# TOP.net
KiCad netlist of a schematic drawn in Altium Designer
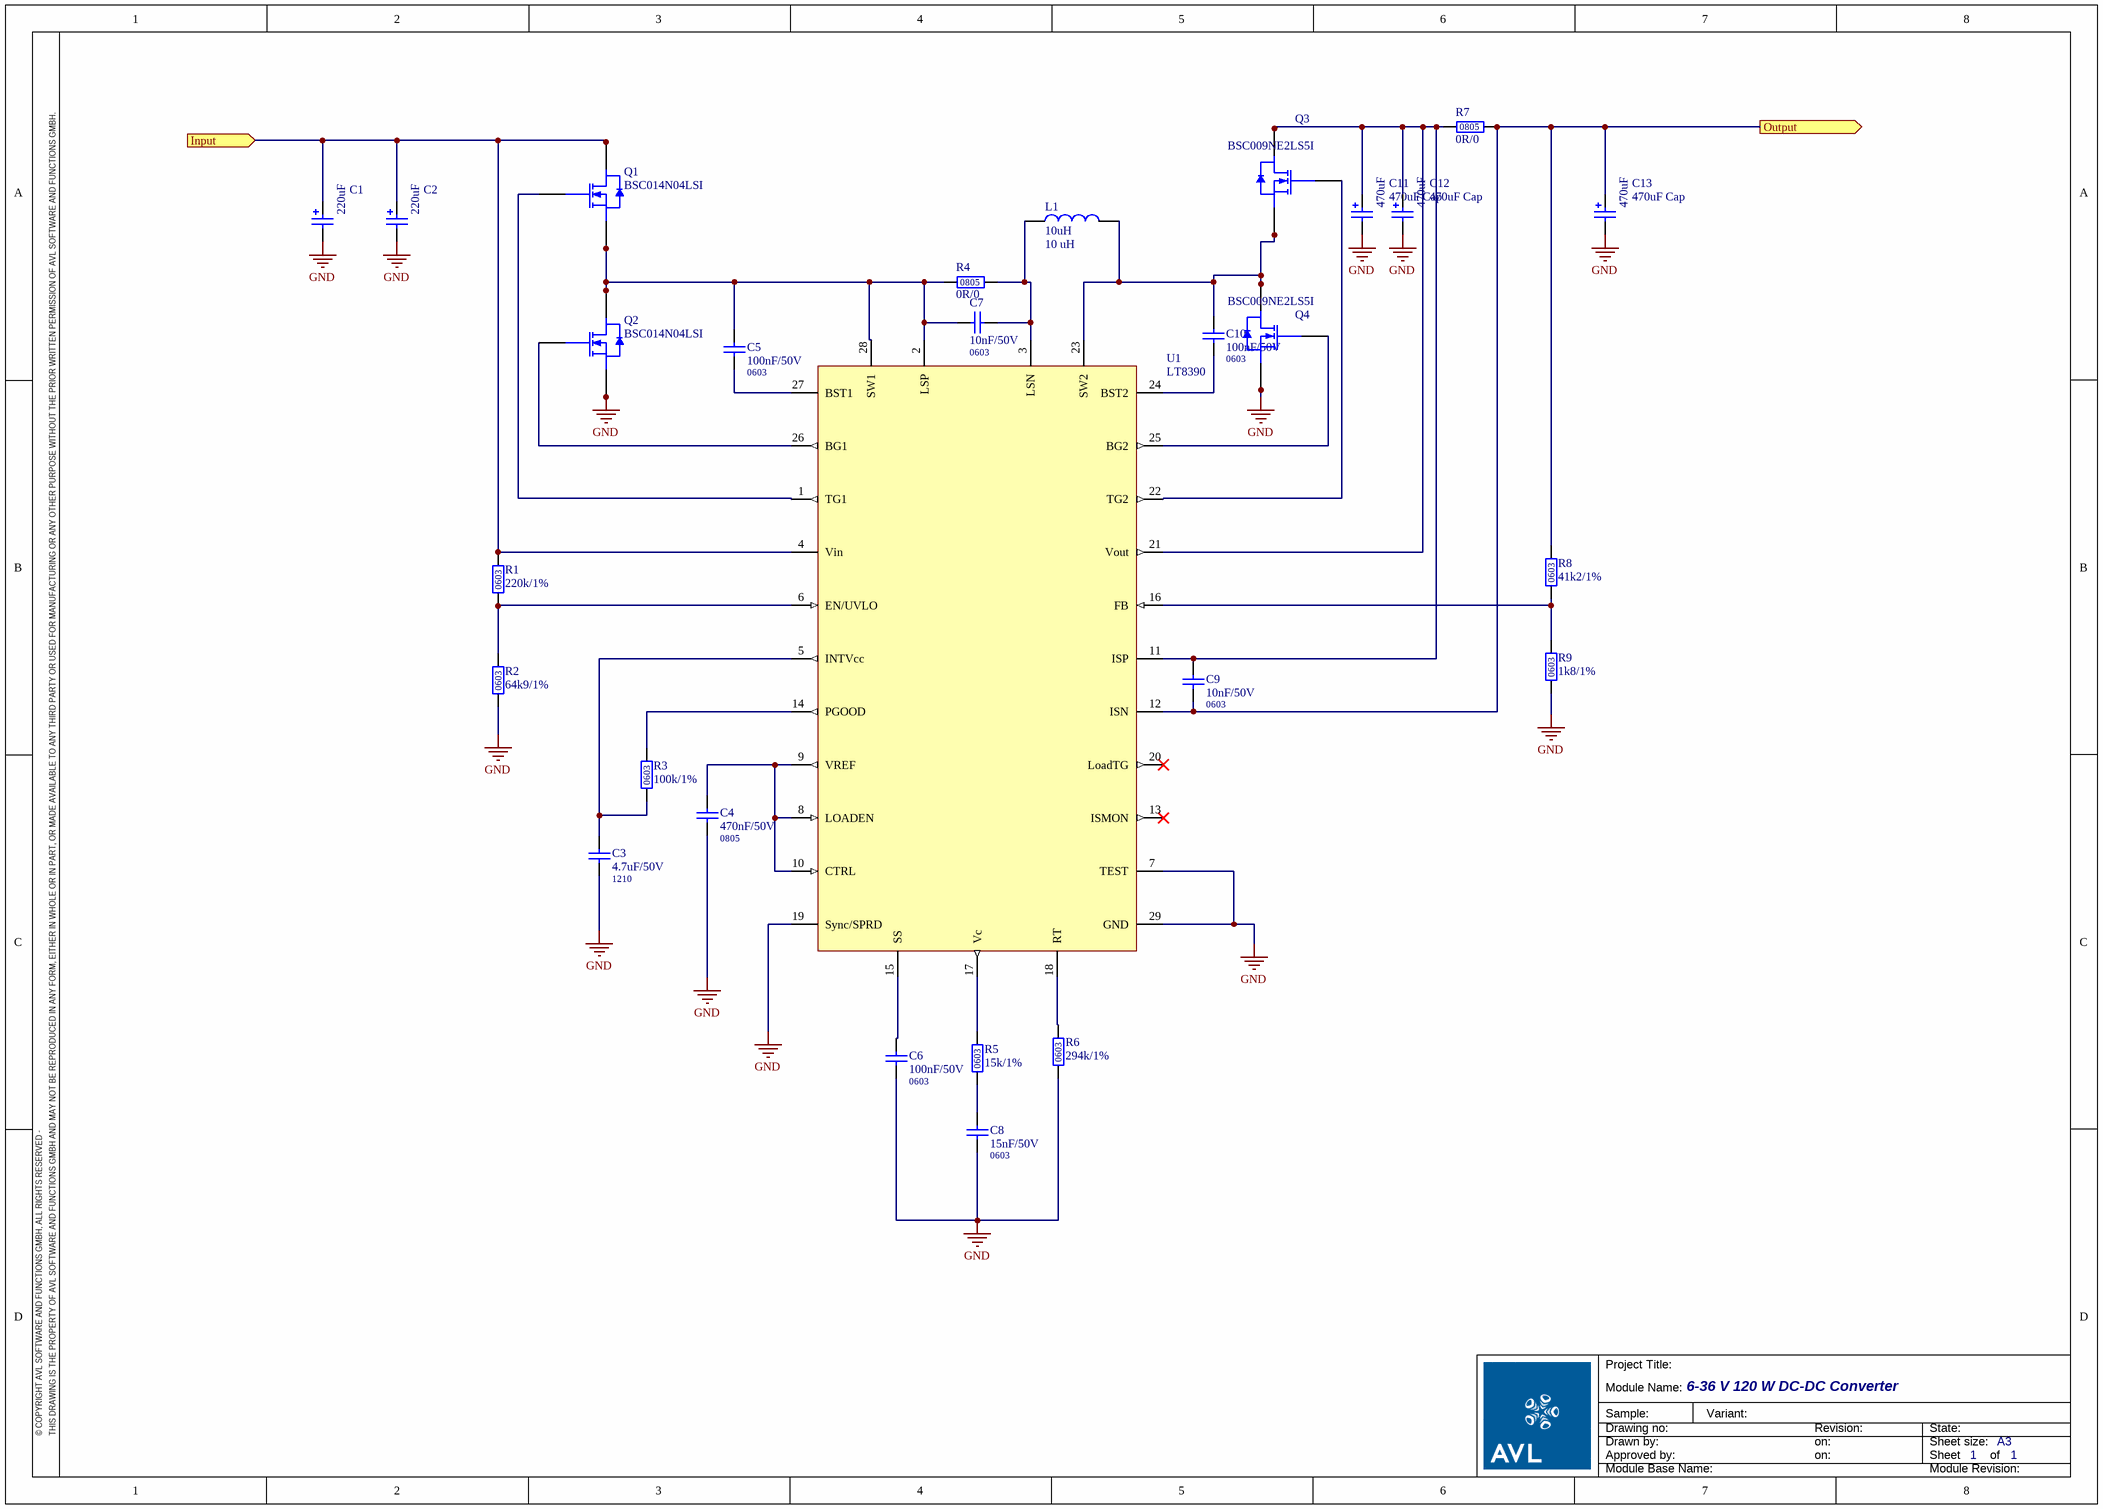
[diagram p0: TOP.SchDoc]

(export (version "E")
  (design (tool "Eeschema 10.0.6"))
  (components
    (comp (ref "C1")
      (value "220uF Cap")
      (footprint "PcbLib:WCAP-ASLI_4x5.5")
      (libsource (lib "SchLib") (part "220uF Cap"))
    )
    (comp (ref "C2")
      (value "220uF Cap")
      (footprint "PcbLib:WCAP-ASLI_4x5.5")
      (libsource (lib "SchLib") (part "220uF Cap"))
    )
    (comp (ref "C3")
      (value "4.7uF/50V")
      (footprint "CAPC3225X30")
      (fields
        (field (name "VOLTAGE") "50V")
        (field (name "PACKAGE") "1210")
        (field (name "PART_NUMBER") "0444.00103")
        (field (name "MANUFACTURER") "Murata")
      )
      (libsource (lib "AVL_EHW_Comp_Lib") (part "Capacitor"))
    )
    (comp (ref "C4")
      (value "470nF/50V")
      (footprint "CAPC2012X15")
      (fields
        (field (name "VOLTAGE") "50V")
        (field (name "PACKAGE") "0805")
        (field (name "PART_NUMBER") "0444.00090")
        (field (name "MANUFACTURER") "Murata")
      )
      (libsource (lib "AVL_EHW_Comp_Lib") (part "Capacitor"))
    )
    (comp (ref "C5")
      (value "100nF/50V")
      (footprint "CAPC1608X10")
      (fields
        (field (name "VOLTAGE") "50V")
        (field (name "PACKAGE") "0603")
        (field (name "PART_NUMBER") "0444.00073")
        (field (name "MANUFACTURER") "Murata")
      )
      (libsource (lib "AVL_EHW_Comp_Lib") (part "Capacitor"))
    )
    (comp (ref "C6")
      (value "100nF/50V")
      (footprint "CAPC1608X10")
      (fields
        (field (name "VOLTAGE") "50V")
        (field (name "PACKAGE") "0603")
        (field (name "PART_NUMBER") "0444.00073")
        (field (name "MANUFACTURER") "Murata")
      )
      (libsource (lib "AVL_EHW_Comp_Lib") (part "Capacitor"))
    )
    (comp (ref "C7")
      (value "10nF/50V")
      (footprint "CAPC1608X10")
      (fields
        (field (name "VOLTAGE") "50V")
        (field (name "PACKAGE") "0603")
        (field (name "PART_NUMBER") "0444.00053")
        (field (name "MANUFACTURER") "Murata")
      )
      (libsource (lib "AVL_EHW_Comp_Lib") (part "Capacitor"))
    )
    (comp (ref "C8")
      (value "15nF/50V")
      (footprint "CAPC1608X10")
      (fields
        (field (name "VOLTAGE") "50V")
        (field (name "PACKAGE") "0603")
        (field (name "PART_NUMBER") "0444.00059")
        (field (name "MANUFACTURER") "Murata")
      )
      (libsource (lib "AVL_EHW_Comp_Lib") (part "Capacitor"))
    )
    (comp (ref "C9")
      (value "10nF/50V")
      (footprint "CAPC1608X10")
      (fields
        (field (name "VOLTAGE") "50V")
        (field (name "PACKAGE") "0603")
        (field (name "PART_NUMBER") "0444.00053")
        (field (name "MANUFACTURER") "Murata")
      )
      (libsource (lib "AVL_EHW_Comp_Lib") (part "Capacitor"))
    )
    (comp (ref "C10")
      (value "100nF/50V")
      (footprint "CAPC1608X10")
      (fields
        (field (name "VOLTAGE") "50V")
        (field (name "PACKAGE") "0603")
        (field (name "PART_NUMBER") "0444.00073")
        (field (name "MANUFACTURER") "Murata")
      )
      (libsource (lib "AVL_EHW_Comp_Lib") (part "Capacitor"))
    )
    (comp (ref "C11")
      (value "470uF Cap")
      (footprint "PcbLib:WCAP-ASLL_4x5.5")
      (libsource (lib "SchLib") (part "470uF Cap"))
    )
    (comp (ref "C12")
      (value "470uF Cap")
      (footprint "PcbLib:WCAP-ASLL_4x5.5")
      (libsource (lib "SchLib") (part "470uF Cap"))
    )
    (comp (ref "C13")
      (value "470uF Cap")
      (footprint "PcbLib:WCAP-ASLL_4x5.5")
      (libsource (lib "SchLib") (part "470uF Cap"))
    )
    (comp (ref "L1")
      (value "10uH")
      (footprint "PcbLib:WE-HCF_2818")
      (description "WE-HCF SMD High Current Inductor, size 2818, 10 uH")
      (fields
        (field (name "PART NUMBER") "7443641000")
        (field (name "ALTIUM_VALUE") "10 uH")
        (field (name "PUBLISHER") "Wurth Elektronik")
      )
      (libsource (lib "SchLib") (part "10uH"))
    )
    (comp (ref "Q1")
      (value "BSC014N04LSI")
      (footprint "PcbLib:TDSON-8-FL")
      (libsource (lib "SchLib") (part "BSC014N04LSI"))
    )
    (comp (ref "Q2")
      (value "BSC014N04LSI")
      (footprint "PcbLib:TDSON-8-FL")
      (libsource (lib "SchLib") (part "BSC014N04LSI"))
    )
    (comp (ref "Q3")
      (value "BSC009NE2LS5I")
      (footprint "PcbLib:TDSON-8-FL")
      (libsource (lib "SchLib") (part "BSC009NE2LS5I"))
    )
    (comp (ref "Q4")
      (value "BSC009NE2LS5I")
      (footprint "PcbLib:TDSON-8-FL")
      (libsource (lib "SchLib") (part "BSC009NE2LS5I"))
    )
    (comp (ref "R1")
      (value "220k/1%")
      (footprint "RESC1608X05")
      (fields
        (field (name "TOLERANCE") "1%")
        (field (name "PACKAGE") "0603")
        (field (name "PART_NUMBER") "0440.00197")
        (field (name "MANUFACTURER") "Vishay")
      )
      (libsource (lib "AVL_EHW_Comp_Lib") (part "Resistor-Chip"))
    )
    (comp (ref "R2")
      (value "64k9/1%")
      (footprint "RESC1608X05")
      (fields
        (field (name "TOLERANCE") "1%")
        (field (name "PACKAGE") "0603")
        (field (name "PART_NUMBER") "0440.00282")
        (field (name "MANUFACTURER") "Vishay")
      )
      (libsource (lib "AVL_EHW_Comp_Lib") (part "Resistor-Chip"))
    )
    (comp (ref "R3")
      (value "100k/1%")
      (footprint "RESC1608X05")
      (fields
        (field (name "TOLERANCE") "1%")
        (field (name "PACKAGE") "0603")
        (field (name "PART_NUMBER") "0440.00176")
        (field (name "MANUFACTURER") "Vishay")
      )
      (libsource (lib "AVL_EHW_Comp_Lib") (part "Resistor-Chip"))
    )
    (comp (ref "R4")
      (value "0R/0")
      (footprint "RESC2012X05")
      (fields
        (field (name "TOLERANCE") "0")
        (field (name "PACKAGE") "0805")
        (field (name "PART_NUMBER") "0440.00003")
        (field (name "MANUFACTURER") "Vishay")
      )
      (libsource (lib "AVL_EHW_Comp_Lib") (part "Resistor-Chip"))
    )
    (comp (ref "R5")
      (value "15k/1%")
      (footprint "RESC1608X05")
      (fields
        (field (name "TOLERANCE") "1%")
        (field (name "PACKAGE") "0603")
        (field (name "PART_NUMBER") "0440.00148")
        (field (name "MANUFACTURER") "Vishay")
      )
      (libsource (lib "AVL_EHW_Comp_Lib") (part "Resistor-Chip"))
    )
    (comp (ref "R6")
      (value "294k/1%")
      (footprint "RESC1608X05")
      (fields
        (field (name "TOLERANCE") "1%")
        (field (name "PACKAGE") "0603")
        (field (name "PART_NUMBER") "0440.00329")
        (field (name "MANUFACTURER") "Vishay")
      )
      (libsource (lib "AVL_EHW_Comp_Lib") (part "Resistor-Chip"))
    )
    (comp (ref "R7")
      (value "0R/0")
      (footprint "RESC2012X05")
      (fields
        (field (name "TOLERANCE") "0")
        (field (name "PACKAGE") "0805")
        (field (name "PART_NUMBER") "0440.00003")
        (field (name "MANUFACTURER") "Vishay")
      )
      (libsource (lib "AVL_EHW_Comp_Lib") (part "Resistor-Chip"))
    )
    (comp (ref "R8")
      (value "41k2/1%")
      (footprint "RESC1608X05")
      (fields
        (field (name "TOLERANCE") "1%")
        (field (name "PACKAGE") "0603")
        (field (name "PART_NUMBER") "0440.00284")
        (field (name "MANUFACTURER") "Vishay")
      )
      (libsource (lib "AVL_EHW_Comp_Lib") (part "Resistor-Chip"))
    )
    (comp (ref "R9")
      (value "1k8/1%")
      (footprint "RESC1608X05")
      (fields
        (field (name "TOLERANCE") "1%")
        (field (name "PACKAGE") "0603")
        (field (name "PART_NUMBER") "0440.00105")
        (field (name "MANUFACTURER") "Vishay")
      )
      (libsource (lib "AVL_EHW_Comp_Lib") (part "Resistor-Chip"))
    )
    (comp (ref "U1")
      (value "LT8390")
      (footprint "LT3890")
      (libsource (lib "Schematic Components") (part "LT8390"))
    )
  )
  (nets
    (net (code "1") (name "/Input") (class "Default")
      (node (ref "C1") (pin "1") (pinfunction "P_1") (pintype "passive"))
      (node (ref "C2") (pin "1") (pinfunction "P_1") (pintype "passive"))
      (node (ref "Q1") (pin "5") (pinfunction "D_5") (pintype "passive"))
      (node (ref "Q1") (pin "6") (pinfunction "D_6") (pintype "passive"))
      (node (ref "Q1") (pin "7") (pinfunction "D_7") (pintype "passive"))
      (node (ref "Q1") (pin "8") (pinfunction "D_8") (pintype "passive"))
      (node (ref "R1") (pin "1") (pinfunction "1_1") (pintype "passive"))
      (node (ref "U1") (pin "4") (pinfunction "Vin_4") (pintype "power_in"))
    )
    (net (code "2") (name "/Output") (class "Default")
      (node (ref "C13") (pin "1") (pinfunction "P_1") (pintype "passive"))
      (node (ref "C9") (pin "2") (pinfunction "2_2") (pintype "passive"))
      (node (ref "R7") (pin "2") (pinfunction "2_2") (pintype "passive"))
      (node (ref "R8") (pin "2") (pinfunction "2_2") (pintype "passive"))
      (node (ref "U1") (pin "12") (pinfunction "ISN_12") (pintype "passive"))
    )
    (net (code "3") (name "GND") (class "Default")
      (node (ref "C1") (pin "2") (pinfunction "N_2") (pintype "passive"))
      (node (ref "C11") (pin "2") (pinfunction "N_2") (pintype "passive"))
      (node (ref "C12") (pin "2") (pinfunction "N_2") (pintype "passive"))
      (node (ref "C13") (pin "2") (pinfunction "N_2") (pintype "passive"))
      (node (ref "C2") (pin "2") (pinfunction "N_2") (pintype "passive"))
      (node (ref "C3") (pin "1") (pinfunction "1_1") (pintype "passive"))
      (node (ref "C4") (pin "1") (pinfunction "1_1") (pintype "passive"))
      (node (ref "C6") (pin "2") (pinfunction "2_2") (pintype "passive"))
      (node (ref "C8") (pin "2") (pinfunction "2_2") (pintype "passive"))
      (node (ref "Q2") (pin "1") (pinfunction "S_1") (pintype "passive"))
      (node (ref "Q2") (pin "2") (pinfunction "S_2") (pintype "passive"))
      (node (ref "Q2") (pin "3") (pinfunction "S_3") (pintype "passive"))
      (node (ref "Q4") (pin "1") (pinfunction "S_1") (pintype "passive"))
      (node (ref "Q4") (pin "2") (pinfunction "S_2") (pintype "passive"))
      (node (ref "Q4") (pin "3") (pinfunction "S_3") (pintype "passive"))
      (node (ref "R2") (pin "2") (pinfunction "2_2") (pintype "passive"))
      (node (ref "R6") (pin "2") (pinfunction "2_2") (pintype "passive"))
      (node (ref "R9") (pin "1") (pinfunction "1_1") (pintype "passive"))
      (node (ref "U1") (pin "19") (pinfunction "Sync/SPRD_19") (pintype "passive"))
      (node (ref "U1") (pin "29") (pinfunction "GND_29") (pintype "power_in"))
      (node (ref "U1") (pin "7") (pinfunction "TEST_7") (pintype "passive"))
    )
    (net (code "4") (name "Net-(C8-Pad1)") (class "Default")
      (node (ref "C8") (pin "1") (pinfunction "1_1") (pintype "passive"))
      (node (ref "R5") (pin "2") (pinfunction "2_2") (pintype "passive"))
    )
    (net (code "5") (name "Net-(C11-P)") (class "Default")
      (node (ref "C11") (pin "1") (pinfunction "P_1") (pintype "passive"))
      (node (ref "C12") (pin "1") (pinfunction "P_1") (pintype "passive"))
      (node (ref "C9") (pin "1") (pinfunction "1_1") (pintype "passive"))
      (node (ref "Q3") (pin "5") (pinfunction "D_5") (pintype "passive"))
      (node (ref "Q3") (pin "6") (pinfunction "D_6") (pintype "passive"))
      (node (ref "Q3") (pin "7") (pinfunction "D_7") (pintype "passive"))
      (node (ref "Q3") (pin "8") (pinfunction "D_8") (pintype "passive"))
      (node (ref "R7") (pin "1") (pinfunction "1_1") (pintype "passive"))
      (node (ref "U1") (pin "11") (pinfunction "ISP_11") (pintype "passive"))
      (node (ref "U1") (pin "21") (pinfunction "Vout_21") (pintype "output"))
    )
    (net (code "6") (name "Net-(Q1-G)") (class "Default")
      (node (ref "Q1") (pin "4") (pinfunction "G_4") (pintype "passive"))
      (node (ref "U1") (pin "1") (pinfunction "TG1_1") (pintype "output"))
    )
    (net (code "7") (name "Net-(Q2-G)") (class "Default")
      (node (ref "Q2") (pin "4") (pinfunction "G_4") (pintype "passive"))
      (node (ref "U1") (pin "26") (pinfunction "BG1_26") (pintype "output"))
    )
    (net (code "8") (name "Net-(Q3-G)") (class "Default")
      (node (ref "Q3") (pin "4") (pinfunction "G_4") (pintype "passive"))
      (node (ref "U1") (pin "22") (pinfunction "TG2_22") (pintype "output"))
    )
    (net (code "9") (name "Net-(Q4-G)") (class "Default")
      (node (ref "Q4") (pin "4") (pinfunction "G_4") (pintype "passive"))
      (node (ref "U1") (pin "25") (pinfunction "BG2_25") (pintype "output"))
    )
    (net (code "10") (name "Net-(U1-BST1)") (class "Default")
      (node (ref "C5") (pin "2") (pinfunction "2_2") (pintype "passive"))
      (node (ref "U1") (pin "27") (pinfunction "BST1_27") (pintype "passive"))
    )
    (net (code "11") (name "Net-(U1-BST2)") (class "Default")
      (node (ref "C10") (pin "2") (pinfunction "2_2") (pintype "passive"))
      (node (ref "U1") (pin "24") (pinfunction "BST2_24") (pintype "passive"))
    )
    (net (code "12") (name "Net-(U1-CTRL)") (class "Default")
      (node (ref "C4") (pin "2") (pinfunction "2_2") (pintype "passive"))
      (node (ref "U1") (pin "10") (pinfunction "CTRL_10") (pintype "input"))
      (node (ref "U1") (pin "8") (pinfunction "LOADEN_8") (pintype "input"))
      (node (ref "U1") (pin "9") (pinfunction "VREF_9") (pintype "output"))
    )
    (net (code "13") (name "Net-(U1-EN{slash}UVLO)") (class "Default")
      (node (ref "R1") (pin "2") (pinfunction "2_2") (pintype "passive"))
      (node (ref "R2") (pin "1") (pinfunction "1_1") (pintype "passive"))
      (node (ref "U1") (pin "6") (pinfunction "EN/UVLO_6") (pintype "input"))
    )
    (net (code "14") (name "Net-(U1-FB)") (class "Default")
      (node (ref "R8") (pin "1") (pinfunction "1_1") (pintype "passive"))
      (node (ref "R9") (pin "2") (pinfunction "2_2") (pintype "passive"))
      (node (ref "U1") (pin "16") (pinfunction "FB_16") (pintype "input"))
    )
    (net (code "15") (name "Net-(U1-INTVcc)") (class "Default")
      (node (ref "C3") (pin "2") (pinfunction "2_2") (pintype "passive"))
      (node (ref "R3") (pin "1") (pinfunction "1_1") (pintype "passive"))
      (node (ref "U1") (pin "5") (pinfunction "INTVcc_5") (pintype "output"))
    )
    (net (code "16") (name "Net-(U1-LSN)") (class "Default")
      (node (ref "C7") (pin "1") (pinfunction "1_1") (pintype "passive"))
      (node (ref "L1") (pin "1") (pinfunction "1_1") (pintype "passive"))
      (node (ref "R4") (pin "2") (pinfunction "2_2") (pintype "passive"))
      (node (ref "U1") (pin "3") (pinfunction "LSN_3") (pintype "passive"))
    )
    (net (code "17") (name "Net-(U1-LSP)") (class "Default")
      (node (ref "C5") (pin "1") (pinfunction "1_1") (pintype "passive"))
      (node (ref "C7") (pin "2") (pinfunction "2_2") (pintype "passive"))
      (node (ref "Q1") (pin "1") (pinfunction "S_1") (pintype "passive"))
      (node (ref "Q1") (pin "2") (pinfunction "S_2") (pintype "passive"))
      (node (ref "Q1") (pin "3") (pinfunction "S_3") (pintype "passive"))
      (node (ref "Q2") (pin "5") (pinfunction "D_5") (pintype "passive"))
      (node (ref "Q2") (pin "6") (pinfunction "D_6") (pintype "passive"))
      (node (ref "Q2") (pin "7") (pinfunction "D_7") (pintype "passive"))
      (node (ref "Q2") (pin "8") (pinfunction "D_8") (pintype "passive"))
      (node (ref "R4") (pin "1") (pinfunction "1_1") (pintype "passive"))
      (node (ref "U1") (pin "2") (pinfunction "LSP_2") (pintype "passive"))
      (node (ref "U1") (pin "28") (pinfunction "SW1_28") (pintype "passive"))
    )
    (net (code "18") (name "Net-(U1-PGOOD)") (class "Default")
      (node (ref "R3") (pin "2") (pinfunction "2_2") (pintype "passive"))
      (node (ref "U1") (pin "14") (pinfunction "PGOOD_14") (pintype "output"))
    )
    (net (code "19") (name "Net-(U1-RT)") (class "Default")
      (node (ref "R6") (pin "1") (pinfunction "1_1") (pintype "passive"))
      (node (ref "U1") (pin "18") (pinfunction "RT_18") (pintype "passive"))
    )
    (net (code "20") (name "Net-(U1-SS)") (class "Default")
      (node (ref "C6") (pin "1") (pinfunction "1_1") (pintype "passive"))
      (node (ref "U1") (pin "15") (pinfunction "SS_15") (pintype "passive"))
    )
    (net (code "21") (name "Net-(U1-SW2)") (class "Default")
      (node (ref "C10") (pin "1") (pinfunction "1_1") (pintype "passive"))
      (node (ref "L1") (pin "2") (pinfunction "2_2") (pintype "passive"))
      (node (ref "Q3") (pin "1") (pinfunction "S_1") (pintype "passive"))
      (node (ref "Q3") (pin "2") (pinfunction "S_2") (pintype "passive"))
      (node (ref "Q3") (pin "3") (pinfunction "S_3") (pintype "passive"))
      (node (ref "Q4") (pin "5") (pinfunction "D_5") (pintype "passive"))
      (node (ref "Q4") (pin "6") (pinfunction "D_6") (pintype "passive"))
      (node (ref "Q4") (pin "7") (pinfunction "D_7") (pintype "passive"))
      (node (ref "Q4") (pin "8") (pinfunction "D_8") (pintype "passive"))
      (node (ref "U1") (pin "23") (pinfunction "SW2_23") (pintype "passive"))
    )
    (net (code "22") (name "Net-(U1-Vc)") (class "Default")
      (node (ref "R5") (pin "1") (pinfunction "1_1") (pintype "passive"))
      (node (ref "U1") (pin "17") (pinfunction "Vc_17") (pintype "output"))
    )
    (net (code "23") (name "unconnected-(U1-ISMON-Pad13)") (class "Default")
      (node (ref "U1") (pin "13") (pinfunction "ISMON_13") (pintype "output+no_connect"))
    )
    (net (code "24") (name "unconnected-(U1-LoadTG-Pad20)") (class "Default")
      (node (ref "U1") (pin "20") (pinfunction "LoadTG_20") (pintype "output+no_connect"))
    )
  )
)
